# MDL-LCD_2X16.net
KiCad netlist of a schematic drawn in Altium Designer
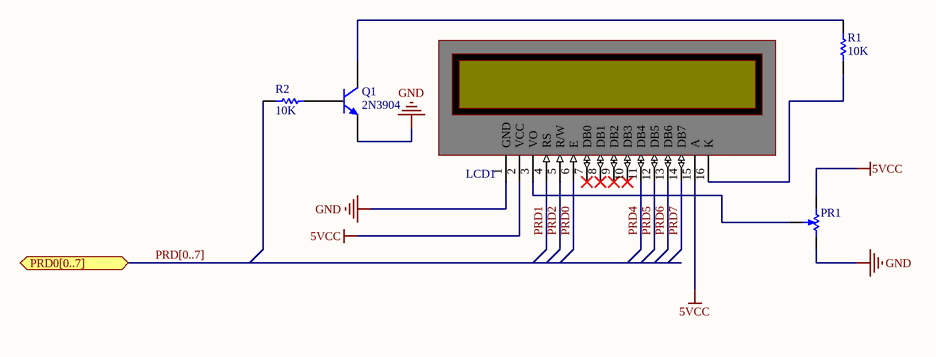
[diagram p0: MDL-LCD_2X16.SchDoc]

(export (version "E")
  (design (tool "Eeschema 10.0.6"))
  (components
    (comp (ref "LCD1")
      (value "LCD 16X2")
      (footprint "LCD 16x2-A")
      (description "LCD 16X2 Character lcd")
      (libsource (lib "LCDs") (part "LCD 16X2"))
    )
    (comp (ref "PR1")
      (value "PT")
      (footprint "potenciometro")
      (description "Square Trimming Potentiometer")
      (fields (field (name "PUBLISHER") "Altium Limited"))
      (libsource (lib "Miscellaneous Devices") (part "RPot SM"))
    )
    (comp (ref "Q1")
      (value "2N3904")
      (footprint "2N3904_OK")
      (description "NPN General Purpose Amplifier")
      (fields (field (name "PUBLISHER") "Altium Limited"))
      (libsource (lib "Miscellaneous Devices") (part "2N3904"))
    )
    (comp (ref "R1")
      (value "10K")
      (footprint "AXIAL-0.3")
      (description "Resistor")
      (fields (field (name "Comment") "Res") (field (name "PUBLISHER") "Altium Limited"))
      (libsource (lib "Miscellaneous Devices") (part "Res1"))
    )
    (comp (ref "R2")
      (value "10K")
      (footprint "AXIAL-0.3")
      (description "Resistor")
      (fields (field (name "Comment") "Res") (field (name "PUBLISHER") "Altium Limited"))
      (libsource (lib "Miscellaneous Devices") (part "Res1"))
    )
  )
  (nets
    (net (code "2") (name "/PRD0") (class "Default")
      (node (ref "LCD1") (pin "6") (pinfunction "E_6") (pintype "input"))
    )
    (net (code "3") (name "/PRD1") (class "Default")
      (node (ref "LCD1") (pin "4") (pinfunction "RS_4") (pintype "input"))
    )
    (net (code "4") (name "/PRD2") (class "Default")
      (node (ref "LCD1") (pin "5") (pinfunction "R/W_5") (pintype "input"))
    )
    (net (code "5") (name "/PRD4") (class "Default")
      (node (ref "LCD1") (pin "11") (pinfunction "DB4_11") (pintype "bidirectional"))
    )
    (net (code "6") (name "/PRD5") (class "Default")
      (node (ref "LCD1") (pin "12") (pinfunction "DB5_12") (pintype "bidirectional"))
    )
    (net (code "7") (name "/PRD6") (class "Default")
      (node (ref "LCD1") (pin "13") (pinfunction "DB6_13") (pintype "bidirectional"))
    )
    (net (code "8") (name "/PRD7") (class "Default")
      (node (ref "LCD1") (pin "14") (pinfunction "DB7_14") (pintype "bidirectional"))
    )
    (net (code "10") (name "5VCC") (class "Default")
      (node (ref "LCD1") (pin "15") (pinfunction "A_15") (pintype "passive"))
      (node (ref "LCD1") (pin "2") (pinfunction "VCC_2") (pintype "power_in"))
      (node (ref "PR1") (pin "CCW") (pinfunction "-_CCW") (pintype "passive"))
    )
    (net (code "11") (name "GND") (class "Default")
      (node (ref "LCD1") (pin "1") (pinfunction "GND_1") (pintype "power_in"))
      (node (ref "PR1") (pin "CW") (pinfunction "+_CW") (pintype "passive"))
      (node (ref "Q1") (pin "1") (pinfunction "E_1") (pintype "passive"))
    )
    (net (code "12") (name "Net-(LCD1-K)") (class "Default")
      (node (ref "LCD1") (pin "16") (pinfunction "K_16") (pintype "passive"))
      (node (ref "R1") (pin "1") (pinfunction "1_1") (pintype "passive"))
    )
    (net (code "13") (name "Net-(LCD1-VO)") (class "Default")
      (node (ref "LCD1") (pin "3") (pinfunction "VO_3") (pintype "passive"))
      (node (ref "PR1") (pin "W") (pinfunction "W_W") (pintype "passive"))
    )
    (net (code "14") (name "Net-(Q1-B)") (class "Default")
      (node (ref "Q1") (pin "2") (pinfunction "B_2") (pintype "passive"))
      (node (ref "R2") (pin "1") (pinfunction "1_1") (pintype "passive"))
    )
    (net (code "15") (name "Net-(Q1-C)") (class "Default")
      (node (ref "Q1") (pin "3") (pinfunction "C_3") (pintype "passive"))
      (node (ref "R1") (pin "2") (pinfunction "2_2") (pintype "passive"))
    )
    (net (code "16") (name "unconnected-(LCD1-DB0-Pad7)") (class "Default")
      (node (ref "LCD1") (pin "7") (pinfunction "DB0_7") (pintype "bidirectional+no_connect"))
    )
    (net (code "17") (name "unconnected-(LCD1-DB1-Pad8)") (class "Default")
      (node (ref "LCD1") (pin "8") (pinfunction "DB1_8") (pintype "bidirectional+no_connect"))
    )
    (net (code "18") (name "unconnected-(LCD1-DB2-Pad9)") (class "Default")
      (node (ref "LCD1") (pin "9") (pinfunction "DB2_9") (pintype "bidirectional+no_connect"))
    )
    (net (code "19") (name "unconnected-(LCD1-DB3-Pad10)") (class "Default")
      (node (ref "LCD1") (pin "10") (pinfunction "DB3_10") (pintype "bidirectional+no_connect"))
    )
    (net (code "20") (name "unconnected-(R2-Pad2)") (class "Default")
      (node (ref "R2") (pin "2") (pinfunction "2_2") (pintype "passive"))
    )
  )
)
